# 24.net
KiCad netlist of a schematic drawn in Altium Designer
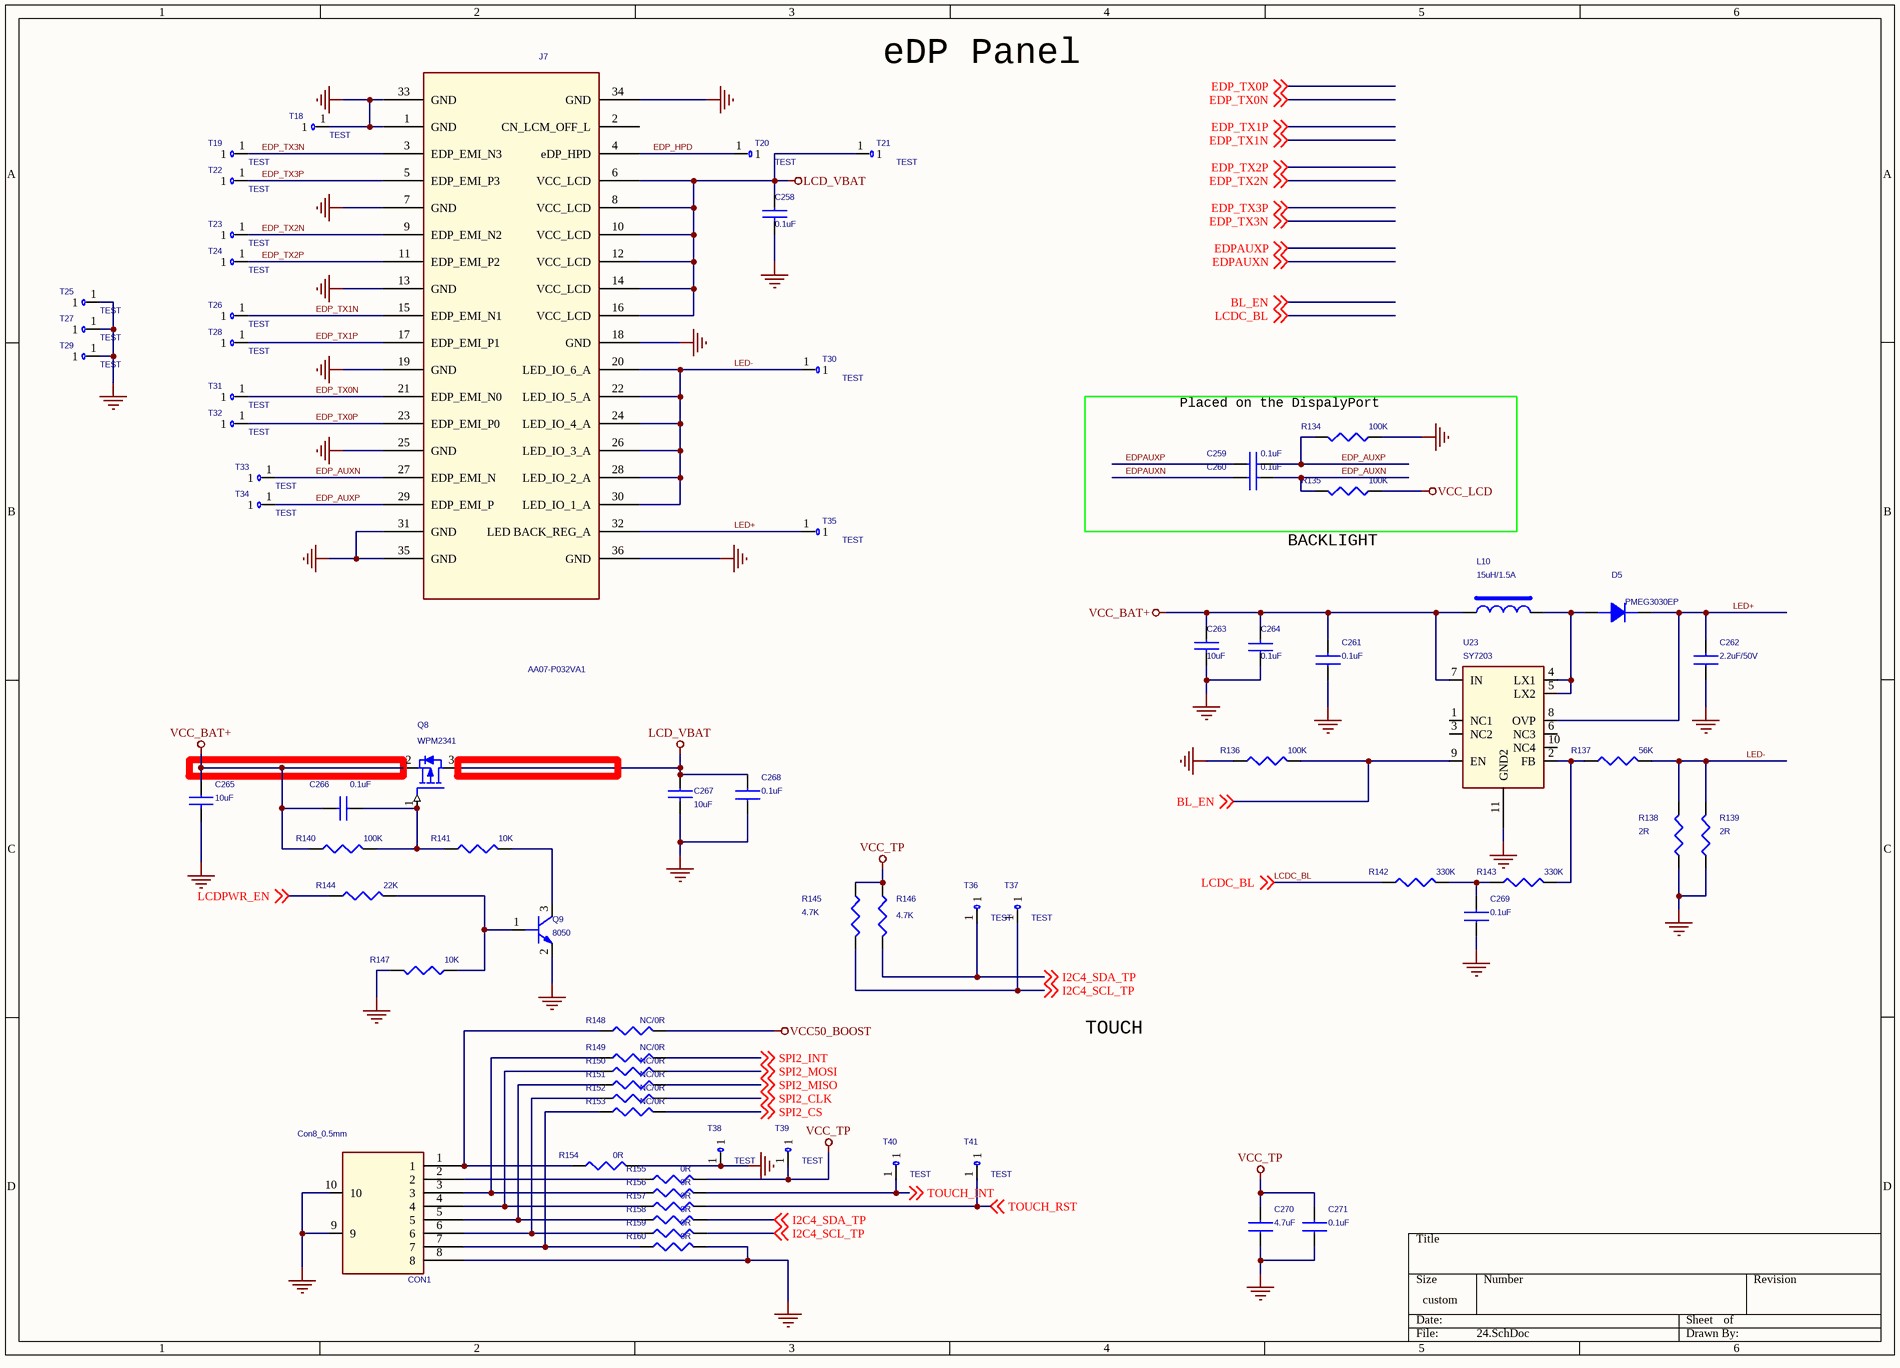
[diagram p0: 24.SchDoc]

(export (version "E")
  (design (tool "Eeschema 10.0.6"))
  (components
    (comp (ref "C258")
      (value "0.1uF")
      (footprint "c0402")
      (description "CAP,MLCC,100nF,+/-10%,X7R,6.3V,SMD0402")
      (libsource (lib "*") (part "CAP NP_3"))
    )
    (comp (ref "C259")
      (value "0.1uF")
      (footprint "c0402")
      (description "CAP,MLCC,100nF,+/-10%,X7R,6.3V,SMD0402")
      (libsource (lib "*") (part "CAP NP_3"))
    )
    (comp (ref "C260")
      (value "0.1uF")
      (footprint "c0402")
      (description "CAP,MLCC,100nF,+/-10%,X7R,6.3V,SMD0402")
      (libsource (lib "*") (part "CAP NP_3"))
    )
    (comp (ref "C261")
      (value "0.1uF")
      (footprint "C0603")
      (description "CAP,MLCC,100nF,+/-10%,X7R,6.3V,SMD0402")
      (libsource (lib "*") (part "CAP NP_Dup3"))
    )
    (comp (ref "C262")
      (value "2.2uF/50V")
      (footprint "C0603")
      (description "RoHS CHIP CAP 1uF +10/-10% 25V X5R")
      (libsource (lib "*") (part "CAP NP_Dup3"))
    )
    (comp (ref "C263") (value "10uF") (footprint "C0603") (libsource (lib "*") (part "C0603")))
    (comp (ref "C264")
      (value "0.1uF")
      (footprint "C0402")
      (description "RoHS CHIP CAP 1uF +10/-10% 16V X5R")
      (libsource (lib "*") (part "CAP NP_Dup2"))
    )
    (comp (ref "C265")
      (value "10uF")
      (footprint "C0603")
      (description "RoHS CHIP CAP 22uF +10/-10% X5R")
      (libsource (lib "*") (part "CAP NP_4"))
    )
    (comp (ref "C266")
      (value "0.1uF")
      (footprint "C0402")
      (description "NC/RoHS CHIP CAP0.1uF +10/-10% X5R")
      (libsource (lib "*") (part "CAP NP_Dup2"))
    )
    (comp (ref "C267")
      (value "10uF")
      (footprint "C0603")
      (description "CAP,MLCC,4.7uF,+/-10%,X5R,6.3V,SMD0603")
      (libsource (lib "*") (part "CAP NP_1_Dup1"))
    )
    (comp (ref "C268")
      (value "0.1uF")
      (footprint "C0603")
      (description "CAP,MLCC,100nF,+/-10%,X7R,6.3V,SMD0402")
      (libsource (lib "*") (part "CAP NP_Dup3"))
    )
    (comp (ref "C269")
      (value "0.1uF")
      (footprint "C0603")
      (description "RoHS CHIP CAP 0.1uF +10/-10% X7R")
      (libsource (lib "*") (part "CAP NP_Dup3"))
    )
    (comp (ref "C270") (value "4.7uF") (footprint "C0603") (libsource (lib "*") (part "CAP NP_Dup3")))
    (comp (ref "C271")
      (value "0.1uF")
      (footprint "C0603")
      (description "CAP,MLCC,100nF,+/-10%,X7R,6.3V,SMD0402")
      (libsource (lib "*") (part "CAP NP_Dup3"))
    )
    (comp (ref "CON1")
      (value "Con8_0.5mm")
      (footprint "BL115H_8RL_TA14")
      (libsource (lib "*") (part "Con8_4.5mm"))
    )
    (comp (ref "D5") (value "PMEG3030EP") (footprint "SOD128") (libsource (lib "*") (part "DIODE_Dup2")))
    (comp (ref "J7")
      (value "AA07-P032VA1")
      (footprint "AA07P032VA1N")
      (description "LCD_CON")
      (libsource (lib "*") (part "A070SN02_0.0"))
    )
    (comp (ref "L10")
      (value "15uH/1.5A")
      (footprint "IND-5X5")
      (libsource (lib "*") (part "INDUCTORS OF FERRITE"))
    )
    (comp (ref "Q8")
      (value "WPM2341")
      (footprint "SOT23")
      (description "NC/MOSFET-P,WPM2341 ,-20V,+/-8V,-2.8A,56m Ohm@Vgs=-2.5V,44m Ohm@Vgs=-4.5V,SOT23")
      (libsource (lib "*") (part "MOSFET N_0"))
    )
    (comp (ref "Q9")
      (value "8050")
      (footprint "SOT23")
      (description "NC/Trans NPN,SS8050,25V,1500mA,10~60@Vce=1V,Ic=500mA, SOT-23")
      (libsource (lib "*") (part "NPN_0_Dup1"))
    )
    (comp (ref "R134") (value "100K") (footprint "r0402") (libsource (lib "*") (part "RESISTOR_1_Dup1")))
    (comp (ref "R135") (value "100K") (footprint "r0402") (libsource (lib "*") (part "RESISTOR_1_Dup1")))
    (comp (ref "R136")
      (value "100K")
      (footprint "r0402")
      (description "ROHS CHIP RES 4.7K 1/16W 5%")
      (libsource (lib "*") (part "RES 1B_Dup1"))
    )
    (comp (ref "R137")
      (value "56K")
      (footprint "r0402")
      (description "ROHS CHIP RES 82K 1/16W 5%")
      (libsource (lib "*") (part "RES 1B_Dup1"))
    )
    (comp (ref "R138")
      (value "2R")
      (footprint "R1206")
      (description "ROHS CHIP RES 4.7R 1/4W 5%")
      (libsource (lib "*") (part "RES 1B_Dup1"))
    )
    (comp (ref "R139")
      (value "2R")
      (footprint "R1206")
      (description "ROHS CHIP RES 4.7R 1/4W 5%")
      (libsource (lib "*") (part "RES 1B_Dup1"))
    )
    (comp (ref "R140")
      (value "100K")
      (footprint "r0402")
      (description "NC/ROHS CHIP RES 100K 1/16W +/-5%")
      (libsource (lib "*") (part "RESISTOR_3"))
    )
    (comp (ref "R141")
      (value "10K")
      (footprint "r0402")
      (description "NC/ROHS CHIP RES 10K 1/16W +/-5%")
      (libsource (lib "*") (part "RESISTOR_3"))
    )
    (comp (ref "R142")
      (value "330K")
      (footprint "r0402")
      (description "ROHS CHIP RES 4.7K 1/16W 5%")
      (libsource (lib "*") (part "RES 1B_Dup1"))
    )
    (comp (ref "R143")
      (value "330K")
      (footprint "r0402")
      (description "ROHS CHIP RES 4.7K 1/16W 5%")
      (libsource (lib "*") (part "RES 1B_Dup1"))
    )
    (comp (ref "R144")
      (value "22K")
      (footprint "r0402")
      (description "NC/ROHS CHIP RES 22K 1/16W +/-5%")
      (libsource (lib "*") (part "RESISTOR_3"))
    )
    (comp (ref "R145")
      (value "4.7K")
      (footprint "R0402")
      (description "ROHS CHIP RES 4.7K 1/16W 5%")
      (libsource (lib "*") (part "RESISTOR_Dup1"))
    )
    (comp (ref "R146")
      (value "4.7K")
      (footprint "R0402")
      (description "ROHS CHIP RES 4.7K 1/16W 5%")
      (libsource (lib "*") (part "RESISTOR_Dup1"))
    )
    (comp (ref "R147")
      (value "10K")
      (footprint "r0402")
      (description "NC/ROHS CHIP RES 10K 1/16W +/-5%")
      (libsource (lib "*") (part "RESISTOR_3"))
    )
    (comp (ref "R148")
      (value "NC/0R")
      (footprint "R0402")
      (description "ROHS CHIP RES 4.7K 1/16W 5%")
      (libsource (lib "*") (part "RESISTOR_Dup1"))
    )
    (comp (ref "R149")
      (value "NC/0R")
      (footprint "R0402")
      (description "ROHS CHIP RES 4.7K 1/16W 5%")
      (libsource (lib "*") (part "RESISTOR_Dup1"))
    )
    (comp (ref "R150")
      (value "NC/0R")
      (footprint "R0402")
      (description "ROHS CHIP RES 4.7K 1/16W 5%")
      (libsource (lib "*") (part "RESISTOR_Dup1"))
    )
    (comp (ref "R151")
      (value "NC/0R")
      (footprint "R0402")
      (description "ROHS CHIP RES 4.7K 1/16W 5%")
      (libsource (lib "*") (part "RESISTOR_Dup1"))
    )
    (comp (ref "R152")
      (value "NC/0R")
      (footprint "R0402")
      (description "ROHS CHIP RES 4.7K 1/16W 5%")
      (libsource (lib "*") (part "RESISTOR_Dup1"))
    )
    (comp (ref "R153")
      (value "NC/0R")
      (footprint "R0402")
      (description "ROHS CHIP RES 4.7K 1/16W 5%")
      (libsource (lib "*") (part "RESISTOR_Dup1"))
    )
    (comp (ref "R154")
      (value "0R")
      (footprint "R0402")
      (description "ROHS CHIP RES 4.7K 1/16W 5%")
      (libsource (lib "*") (part "RESISTOR_Dup1"))
    )
    (comp (ref "R155")
      (value "0R")
      (footprint "R0402")
      (description "ROHS CHIP RES 4.7K 1/16W 5%")
      (libsource (lib "*") (part "RESISTOR_Dup1"))
    )
    (comp (ref "R156")
      (value "0R")
      (footprint "R0402")
      (description "ROHS CHIP RES 4.7K 1/16W 5%")
      (libsource (lib "*") (part "RESISTOR_Dup1"))
    )
    (comp (ref "R157")
      (value "0R")
      (footprint "R0402")
      (description "ROHS CHIP RES 4.7K 1/16W 5%")
      (libsource (lib "*") (part "RESISTOR_Dup1"))
    )
    (comp (ref "R158")
      (value "0R")
      (footprint "R0402")
      (description "ROHS CHIP RES 4.7K 1/16W 5%")
      (libsource (lib "*") (part "RESISTOR_Dup1"))
    )
    (comp (ref "R159")
      (value "0R")
      (footprint "R0402")
      (description "ROHS CHIP RES 4.7K 1/16W 5%")
      (libsource (lib "*") (part "RESISTOR_Dup1"))
    )
    (comp (ref "R160")
      (value "0R")
      (footprint "R0402")
      (description "ROHS CHIP RES 4.7K 1/16W 5%")
      (libsource (lib "*") (part "RESISTOR_Dup1"))
    )
    (comp (ref "T18") (value "TEST") (footprint "TEST") (libsource (lib "*") (part "TEST_0")))
    (comp (ref "T19") (value "TEST") (footprint "TEST") (libsource (lib "*") (part "TEST_0")))
    (comp (ref "T20") (value "TEST") (footprint "TEST") (libsource (lib "") (part "TEST_0_1")))
    (comp (ref "T21") (value "TEST") (footprint "TEST") (libsource (lib "") (part "TEST_0_1")))
    (comp (ref "T22") (value "TEST") (footprint "TEST") (libsource (lib "*") (part "TEST_0")))
    (comp (ref "T23") (value "TEST") (footprint "TEST") (libsource (lib "*") (part "TEST_0")))
    (comp (ref "T24") (value "TEST") (footprint "TEST") (libsource (lib "*") (part "TEST_0")))
    (comp (ref "T25") (value "TEST") (footprint "TEST") (libsource (lib "*") (part "TEST_0")))
    (comp (ref "T26") (value "TEST") (footprint "TEST") (libsource (lib "*") (part "TEST_0")))
    (comp (ref "T27") (value "TEST") (footprint "TEST") (libsource (lib "*") (part "TEST_0")))
    (comp (ref "T28") (value "TEST") (footprint "TEST") (libsource (lib "*") (part "TEST_0")))
    (comp (ref "T29") (value "TEST") (footprint "TEST") (libsource (lib "*") (part "TEST_0")))
    (comp (ref "T30") (value "TEST") (footprint "TEST") (libsource (lib "") (part "TEST_0_1")))
    (comp (ref "T31") (value "TEST") (footprint "TEST") (libsource (lib "*") (part "TEST_0")))
    (comp (ref "T32") (value "TEST") (footprint "TEST") (libsource (lib "*") (part "TEST_0")))
    (comp (ref "T33") (value "TEST") (footprint "TEST") (libsource (lib "*") (part "TEST_0")))
    (comp (ref "T34") (value "TEST") (footprint "TEST") (libsource (lib "*") (part "TEST_0")))
    (comp (ref "T35") (value "TEST") (footprint "TEST") (libsource (lib "") (part "TEST_0_1")))
    (comp (ref "T36") (value "TEST") (footprint "TEST") (libsource (lib "*") (part "TEST_0")))
    (comp (ref "T37") (value "TEST") (footprint "TEST") (libsource (lib "*") (part "TEST_0")))
    (comp (ref "T38") (value "TEST") (footprint "TEST") (libsource (lib "*") (part "TEST_0")))
    (comp (ref "T39") (value "TEST") (footprint "TEST") (libsource (lib "*") (part "TEST_0")))
    (comp (ref "T40") (value "TEST") (footprint "TEST") (libsource (lib "*") (part "TEST_0")))
    (comp (ref "T41") (value "TEST") (footprint "TEST") (libsource (lib "*") (part "TEST_0")))
    (comp (ref "U23") (value "SY7203") (footprint "QFN8-2X2") (libsource (lib "*") (part "MP3202-QFN8_1")))
  )
  (nets
    (net (code "1") (name "/EDP_AUXN") (class "Default")
      (node (ref "C260") (pin "2") (pinfunction "2_2") (pintype "passive"))
      (node (ref "J7") (pin "27") (pinfunction "EDP_EMI_N_27") (pintype "passive"))
      (node (ref "R135") (pin "1") (pinfunction "1_1") (pintype "passive"))
      (node (ref "T33") (pin "1") (pinfunction "1_1") (pintype "passive"))
    )
    (net (code "2") (name "/EDP_AUXP") (class "Default")
      (node (ref "C259") (pin "2") (pinfunction "2_2") (pintype "passive"))
      (node (ref "J7") (pin "29") (pinfunction "EDP_EMI_P_29") (pintype "passive"))
      (node (ref "R134") (pin "1") (pinfunction "1_1") (pintype "passive"))
      (node (ref "T34") (pin "1") (pinfunction "1_1") (pintype "passive"))
    )
    (net (code "3") (name "/EDP_HPD") (class "Default")
      (node (ref "J7") (pin "4") (pinfunction "eDP_HPD_4") (pintype "passive"))
      (node (ref "T20") (pin "1") (pinfunction "1_1") (pintype "passive"))
    )
    (net (code "4") (name "/LED+") (class "Default")
      (node (ref "C262") (pin "1") (pinfunction "1_1") (pintype "passive"))
      (node (ref "D5") (pin "2") (pinfunction "K_2") (pintype "passive"))
      (node (ref "J7") (pin "32") (pinfunction "LED_BACK_REG_A_32") (pintype "passive"))
      (node (ref "T35") (pin "1") (pinfunction "1_1") (pintype "passive"))
      (node (ref "U23") (pin "8") (pinfunction "OVP_8") (pintype "passive"))
    )
    (net (code "5") (name "/LED-") (class "Default")
      (node (ref "J7") (pin "20") (pinfunction "LED_IO_6_A_20") (pintype "passive"))
      (node (ref "J7") (pin "22") (pinfunction "LED_IO_5_A_22") (pintype "passive"))
      (node (ref "J7") (pin "24") (pinfunction "LED_IO_4_A_24") (pintype "passive"))
      (node (ref "J7") (pin "26") (pinfunction "LED_IO_3_A_26") (pintype "passive"))
      (node (ref "J7") (pin "28") (pinfunction "LED_IO_2_A_28") (pintype "passive"))
      (node (ref "J7") (pin "30") (pinfunction "LED_IO_1_A_30") (pintype "passive"))
      (node (ref "R137") (pin "2") (pinfunction "2_2") (pintype "passive"))
      (node (ref "R138") (pin "1") (pinfunction "1_1") (pintype "passive"))
      (node (ref "R139") (pin "1") (pinfunction "1_1") (pintype "passive"))
      (node (ref "T30") (pin "1") (pinfunction "1_1") (pintype "passive"))
    )
    (net (code "6") (name "BL_EN") (class "Default")
      (node (ref "R136") (pin "2") (pinfunction "2_2") (pintype "passive"))
      (node (ref "U23") (pin "9") (pinfunction "EN_9") (pintype "passive"))
    )
    (net (code "7") (name "EDPAUXN") (class "Default")
      (node (ref "C260") (pin "1") (pinfunction "1_1") (pintype "passive"))
    )
    (net (code "8") (name "EDPAUXP") (class "Default")
      (node (ref "C259") (pin "1") (pinfunction "1_1") (pintype "passive"))
    )
    (net (code "9") (name "EDP_TX0N") (class "Default")
      (node (ref "J7") (pin "21") (pinfunction "EDP_EMI_N0_21") (pintype "passive"))
      (node (ref "T31") (pin "1") (pinfunction "1_1") (pintype "passive"))
    )
    (net (code "10") (name "EDP_TX0P") (class "Default")
      (node (ref "J7") (pin "23") (pinfunction "EDP_EMI_P0_23") (pintype "passive"))
      (node (ref "T32") (pin "1") (pinfunction "1_1") (pintype "passive"))
    )
    (net (code "11") (name "EDP_TX1N") (class "Default")
      (node (ref "J7") (pin "15") (pinfunction "EDP_EMI_N1_15") (pintype "passive"))
      (node (ref "T26") (pin "1") (pinfunction "1_1") (pintype "passive"))
    )
    (net (code "12") (name "EDP_TX1P") (class "Default")
      (node (ref "J7") (pin "17") (pinfunction "EDP_EMI_P1_17") (pintype "passive"))
      (node (ref "T28") (pin "1") (pinfunction "1_1") (pintype "passive"))
    )
    (net (code "13") (name "EDP_TX2N") (class "Default")
      (node (ref "J7") (pin "9") (pinfunction "EDP_EMI_N2_9") (pintype "passive"))
      (node (ref "T23") (pin "1") (pinfunction "1_1") (pintype "passive"))
    )
    (net (code "14") (name "EDP_TX2P") (class "Default")
      (node (ref "J7") (pin "11") (pinfunction "EDP_EMI_P2_11") (pintype "passive"))
      (node (ref "T24") (pin "1") (pinfunction "1_1") (pintype "passive"))
    )
    (net (code "15") (name "EDP_TX3N") (class "Default")
      (node (ref "J7") (pin "3") (pinfunction "EDP_EMI_N3_3") (pintype "passive"))
      (node (ref "T19") (pin "1") (pinfunction "1_1") (pintype "passive"))
    )
    (net (code "16") (name "EDP_TX3P") (class "Default")
      (node (ref "J7") (pin "5") (pinfunction "EDP_EMI_P3_5") (pintype "passive"))
      (node (ref "T22") (pin "1") (pinfunction "1_1") (pintype "passive"))
    )
    (net (code "17") (name "GND") (class "Default")
      (node (ref "C258") (pin "2") (pinfunction "2_2") (pintype "passive"))
      (node (ref "C261") (pin "2") (pinfunction "2_2") (pintype "passive"))
      (node (ref "C262") (pin "2") (pinfunction "2_2") (pintype "passive"))
      (node (ref "C263") (pin "2") (pinfunction "2_2") (pintype "passive"))
      (node (ref "C264") (pin "1") (pinfunction "1_1") (pintype "passive"))
      (node (ref "C265") (pin "2") (pinfunction "2_2") (pintype "passive"))
      (node (ref "C267") (pin "2") (pinfunction "2_2") (pintype "passive"))
      (node (ref "C268") (pin "2") (pinfunction "2_2") (pintype "passive"))
      (node (ref "C269") (pin "1") (pinfunction "1_1") (pintype "passive"))
      (node (ref "C270") (pin "2") (pinfunction "2_2") (pintype "passive"))
      (node (ref "C271") (pin "2") (pinfunction "2_2") (pintype "passive"))
      (node (ref "CON1") (pin "10") (pinfunction "10_10") (pintype "passive"))
      (node (ref "CON1") (pin "8") (pinfunction "8_8") (pintype "passive"))
      (node (ref "CON1") (pin "9") (pinfunction "9_9") (pintype "passive"))
      (node (ref "J7") (pin "1") (pinfunction "GND_1") (pintype "power_in"))
      (node (ref "J7") (pin "13") (pinfunction "GND_13") (pintype "power_in"))
      (node (ref "J7") (pin "18") (pinfunction "GND_18") (pintype "power_in"))
      (node (ref "J7") (pin "19") (pinfunction "GND_19") (pintype "power_in"))
      (node (ref "J7") (pin "25") (pinfunction "GND_25") (pintype "power_in"))
      (node (ref "J7") (pin "31") (pinfunction "GND_31") (pintype "power_in"))
      (node (ref "J7") (pin "33") (pinfunction "GND_33") (pintype "power_in"))
      (node (ref "J7") (pin "34") (pinfunction "GND_34") (pintype "power_in"))
      (node (ref "J7") (pin "35") (pinfunction "GND_35") (pintype "power_in"))
      (node (ref "J7") (pin "36") (pinfunction "GND_36") (pintype "power_in"))
      (node (ref "J7") (pin "7") (pinfunction "GND_7") (pintype "power_in"))
      (node (ref "Q9") (pin "2") (pinfunction "2_2") (pintype "passive"))
      (node (ref "R134") (pin "2") (pinfunction "2_2") (pintype "passive"))
      (node (ref "R136") (pin "1") (pinfunction "1_1") (pintype "passive"))
      (node (ref "R138") (pin "2") (pinfunction "2_2") (pintype "passive"))
      (node (ref "R139") (pin "2") (pinfunction "2_2") (pintype "passive"))
      (node (ref "R147") (pin "1") (pinfunction "1_1") (pintype "passive"))
      (node (ref "R154") (pin "2") (pinfunction "2_2") (pintype "passive"))
      (node (ref "R160") (pin "2") (pinfunction "2_2") (pintype "passive"))
      (node (ref "T18") (pin "1") (pinfunction "1_1") (pintype "passive"))
      (node (ref "T25") (pin "1") (pinfunction "1_1") (pintype "passive"))
      (node (ref "T27") (pin "1") (pinfunction "1_1") (pintype "passive"))
      (node (ref "T29") (pin "1") (pinfunction "1_1") (pintype "passive"))
      (node (ref "T38") (pin "1") (pinfunction "1_1") (pintype "passive"))
      (node (ref "U23") (pin "11") (pinfunction "GND2_11") (pintype "passive"))
    )
    (net (code "18") (name "I2C4_SCL_TP") (class "Default")
      (node (ref "R145") (pin "2") (pinfunction "2_2") (pintype "passive"))
      (node (ref "R159") (pin "2") (pinfunction "2_2") (pintype "passive"))
      (node (ref "T37") (pin "1") (pinfunction "1_1") (pintype "passive"))
    )
    (net (code "19") (name "I2C4_SDA_TP") (class "Default")
      (node (ref "R146") (pin "2") (pinfunction "2_2") (pintype "passive"))
      (node (ref "R158") (pin "2") (pinfunction "2_2") (pintype "passive"))
      (node (ref "T36") (pin "1") (pinfunction "1_1") (pintype "passive"))
    )
    (net (code "20") (name "LCDC_BL") (class "Default")
      (node (ref "R142") (pin "1") (pinfunction "1_1") (pintype "passive"))
    )
    (net (code "21") (name "LCDPWR_EN") (class "Default")
      (node (ref "R144") (pin "2") (pinfunction "2_2") (pintype "passive"))
    )
    (net (code "22") (name "LCD_VBAT") (class "Default")
      (node (ref "C258") (pin "1") (pinfunction "1_1") (pintype "passive"))
      (node (ref "C267") (pin "1") (pinfunction "1_1") (pintype "passive"))
      (node (ref "C268") (pin "1") (pinfunction "1_1") (pintype "passive"))
      (node (ref "J7") (pin "10") (pinfunction "VCC_LCD_10") (pintype "power_in"))
      (node (ref "J7") (pin "12") (pinfunction "VCC_LCD_12") (pintype "power_in"))
      (node (ref "J7") (pin "14") (pinfunction "VCC_LCD_14") (pintype "power_in"))
      (node (ref "J7") (pin "16") (pinfunction "VCC_LCD_16") (pintype "power_in"))
      (node (ref "J7") (pin "6") (pinfunction "VCC_LCD_6") (pintype "power_in"))
      (node (ref "J7") (pin "8") (pinfunction "VCC_LCD_8") (pintype "power_in"))
      (node (ref "Q8") (pin "3") (pinfunction "DRAIN_3") (pintype "passive"))
      (node (ref "T21") (pin "1") (pinfunction "1_1") (pintype "passive"))
    )
    (net (code "23") (name "Net-(C269-Pad2)") (class "Default")
      (node (ref "C269") (pin "2") (pinfunction "2_2") (pintype "passive"))
      (node (ref "R142") (pin "2") (pinfunction "2_2") (pintype "passive"))
      (node (ref "R143") (pin "1") (pinfunction "1_1") (pintype "passive"))
    )
    (net (code "24") (name "Net-(CON1-Pad1)") (class "Default")
      (node (ref "CON1") (pin "1") (pinfunction "1_1") (pintype "passive"))
      (node (ref "R148") (pin "1") (pinfunction "1_1") (pintype "passive"))
      (node (ref "R154") (pin "1") (pinfunction "1_1") (pintype "passive"))
    )
    (net (code "25") (name "Net-(CON1-Pad2)") (class "Default")
      (node (ref "CON1") (pin "2") (pinfunction "2_2") (pintype "passive"))
      (node (ref "R155") (pin "1") (pinfunction "1_1") (pintype "passive"))
    )
    (net (code "26") (name "Net-(CON1-Pad3)") (class "Default")
      (node (ref "CON1") (pin "3") (pinfunction "3_3") (pintype "passive"))
      (node (ref "R149") (pin "1") (pinfunction "1_1") (pintype "passive"))
      (node (ref "R156") (pin "1") (pinfunction "1_1") (pintype "passive"))
    )
    (net (code "27") (name "Net-(CON1-Pad4)") (class "Default")
      (node (ref "CON1") (pin "4") (pinfunction "4_4") (pintype "passive"))
      (node (ref "R150") (pin "1") (pinfunction "1_1") (pintype "passive"))
      (node (ref "R157") (pin "1") (pinfunction "1_1") (pintype "passive"))
    )
    (net (code "28") (name "Net-(CON1-Pad5)") (class "Default")
      (node (ref "CON1") (pin "5") (pinfunction "5_5") (pintype "passive"))
      (node (ref "R151") (pin "1") (pinfunction "1_1") (pintype "passive"))
      (node (ref "R158") (pin "1") (pinfunction "1_1") (pintype "passive"))
    )
    (net (code "29") (name "Net-(CON1-Pad6)") (class "Default")
      (node (ref "CON1") (pin "6") (pinfunction "6_6") (pintype "passive"))
      (node (ref "R152") (pin "1") (pinfunction "1_1") (pintype "passive"))
      (node (ref "R159") (pin "1") (pinfunction "1_1") (pintype "passive"))
    )
    (net (code "30") (name "Net-(CON1-Pad7)") (class "Default")
      (node (ref "CON1") (pin "7") (pinfunction "7_7") (pintype "passive"))
      (node (ref "R153") (pin "1") (pinfunction "1_1") (pintype "passive"))
      (node (ref "R160") (pin "1") (pinfunction "1_1") (pintype "passive"))
    )
    (net (code "31") (name "Net-(D5-A)") (class "Default")
      (node (ref "D5") (pin "1") (pinfunction "A_1") (pintype "passive"))
      (node (ref "L10") (pin "2") (pinfunction "2_2") (pintype "passive"))
      (node (ref "U23") (pin "4") (pinfunction "LX1_4") (pintype "passive"))
      (node (ref "U23") (pin "5") (pinfunction "LX2_5") (pintype "passive"))
    )
    (net (code "32") (name "Net-(Q8-GATE)") (class "Default")
      (node (ref "C266") (pin "1") (pinfunction "1_1") (pintype "passive"))
      (node (ref "Q8") (pin "1") (pinfunction "GATE_1") (pintype "input"))
      (node (ref "R140") (pin "1") (pinfunction "1_1") (pintype "passive"))
      (node (ref "R141") (pin "2") (pinfunction "2_2") (pintype "passive"))
    )
    (net (code "33") (name "Net-(Q9-Pad1)") (class "Default")
      (node (ref "Q9") (pin "1") (pinfunction "1_1") (pintype "passive"))
      (node (ref "R144") (pin "1") (pinfunction "1_1") (pintype "passive"))
      (node (ref "R147") (pin "2") (pinfunction "2_2") (pintype "passive"))
    )
    (net (code "34") (name "Net-(Q9-Pad3)") (class "Default")
      (node (ref "Q9") (pin "3") (pinfunction "3_3") (pintype "passive"))
      (node (ref "R141") (pin "1") (pinfunction "1_1") (pintype "passive"))
    )
    (net (code "35") (name "Net-(U23-FB)") (class "Default")
      (node (ref "R137") (pin "1") (pinfunction "1_1") (pintype "passive"))
      (node (ref "R143") (pin "2") (pinfunction "2_2") (pintype "passive"))
      (node (ref "U23") (pin "2") (pinfunction "FB_2") (pintype "passive"))
    )
    (net (code "36") (name "SPI2_CLK") (class "Default")
      (node (ref "R152") (pin "2") (pinfunction "2_2") (pintype "passive"))
    )
    (net (code "37") (name "SPI2_CS") (class "Default")
      (node (ref "R153") (pin "2") (pinfunction "2_2") (pintype "passive"))
    )
    (net (code "38") (name "SPI2_INT") (class "Default")
      (node (ref "R149") (pin "2") (pinfunction "2_2") (pintype "passive"))
    )
    (net (code "39") (name "SPI2_MISO") (class "Default")
      (node (ref "R151") (pin "2") (pinfunction "2_2") (pintype "passive"))
    )
    (net (code "40") (name "SPI2_MOSI") (class "Default")
      (node (ref "R150") (pin "2") (pinfunction "2_2") (pintype "passive"))
    )
    (net (code "41") (name "TOUCH_INT") (class "Default")
      (node (ref "R156") (pin "2") (pinfunction "2_2") (pintype "passive"))
      (node (ref "T40") (pin "1") (pinfunction "1_1") (pintype "passive"))
    )
    (net (code "42") (name "TOUCH_RST") (class "Default")
      (node (ref "R157") (pin "2") (pinfunction "2_2") (pintype "passive"))
      (node (ref "T41") (pin "1") (pinfunction "1_1") (pintype "passive"))
    )
    (net (code "43") (name "VCC50_BOOST") (class "Default")
      (node (ref "R148") (pin "2") (pinfunction "2_2") (pintype "passive"))
    )
    (net (code "44") (name "VCC_BAT+") (class "Default")
      (node (ref "C261") (pin "1") (pinfunction "1_1") (pintype "passive"))
      (node (ref "C263") (pin "1") (pinfunction "1_1") (pintype "passive"))
      (node (ref "C264") (pin "2") (pinfunction "2_2") (pintype "passive"))
      (node (ref "C265") (pin "1") (pinfunction "1_1") (pintype "passive"))
      (node (ref "C266") (pin "2") (pinfunction "2_2") (pintype "passive"))
      (node (ref "L10") (pin "1") (pinfunction "1_1") (pintype "passive"))
      (node (ref "Q8") (pin "2") (pinfunction "SOURCE_2") (pintype "passive"))
      (node (ref "R140") (pin "2") (pinfunction "2_2") (pintype "passive"))
      (node (ref "U23") (pin "7") (pinfunction "IN_7") (pintype "passive"))
    )
    (net (code "45") (name "VCC_LCD") (class "Default")
      (node (ref "R135") (pin "2") (pinfunction "2_2") (pintype "passive"))
    )
    (net (code "46") (name "VCC_TP") (class "Default")
      (node (ref "C270") (pin "1") (pinfunction "1_1") (pintype "passive"))
      (node (ref "C271") (pin "1") (pinfunction "1_1") (pintype "passive"))
      (node (ref "R145") (pin "1") (pinfunction "1_1") (pintype "passive"))
      (node (ref "R146") (pin "1") (pinfunction "1_1") (pintype "passive"))
      (node (ref "R155") (pin "2") (pinfunction "2_2") (pintype "passive"))
      (node (ref "T39") (pin "1") (pinfunction "1_1") (pintype "passive"))
    )
    (net (code "47") (name "unconnected-(J7-CN_LCM_OFF_L-Pad2)") (class "Default")
      (node (ref "J7") (pin "2") (pinfunction "CN_LCM_OFF_L_2") (pintype "passive"))
    )
    (net (code "48") (name "unconnected-(U23-NC1-Pad1)") (class "Default")
      (node (ref "U23") (pin "1") (pinfunction "NC1_1") (pintype "passive"))
    )
    (net (code "49") (name "unconnected-(U23-NC2-Pad3)") (class "Default")
      (node (ref "U23") (pin "3") (pinfunction "NC2_3") (pintype "passive"))
    )
    (net (code "50") (name "unconnected-(U23-NC3-Pad6)") (class "Default")
      (node (ref "U23") (pin "6") (pinfunction "NC3_6") (pintype "passive"))
    )
    (net (code "51") (name "unconnected-(U23-NC4-Pad10)") (class "Default")
      (node (ref "U23") (pin "10") (pinfunction "NC4_10") (pintype "passive"))
    )
  )
)
